# atmega.net
KiCad netlist of a schematic drawn in Altium Designer
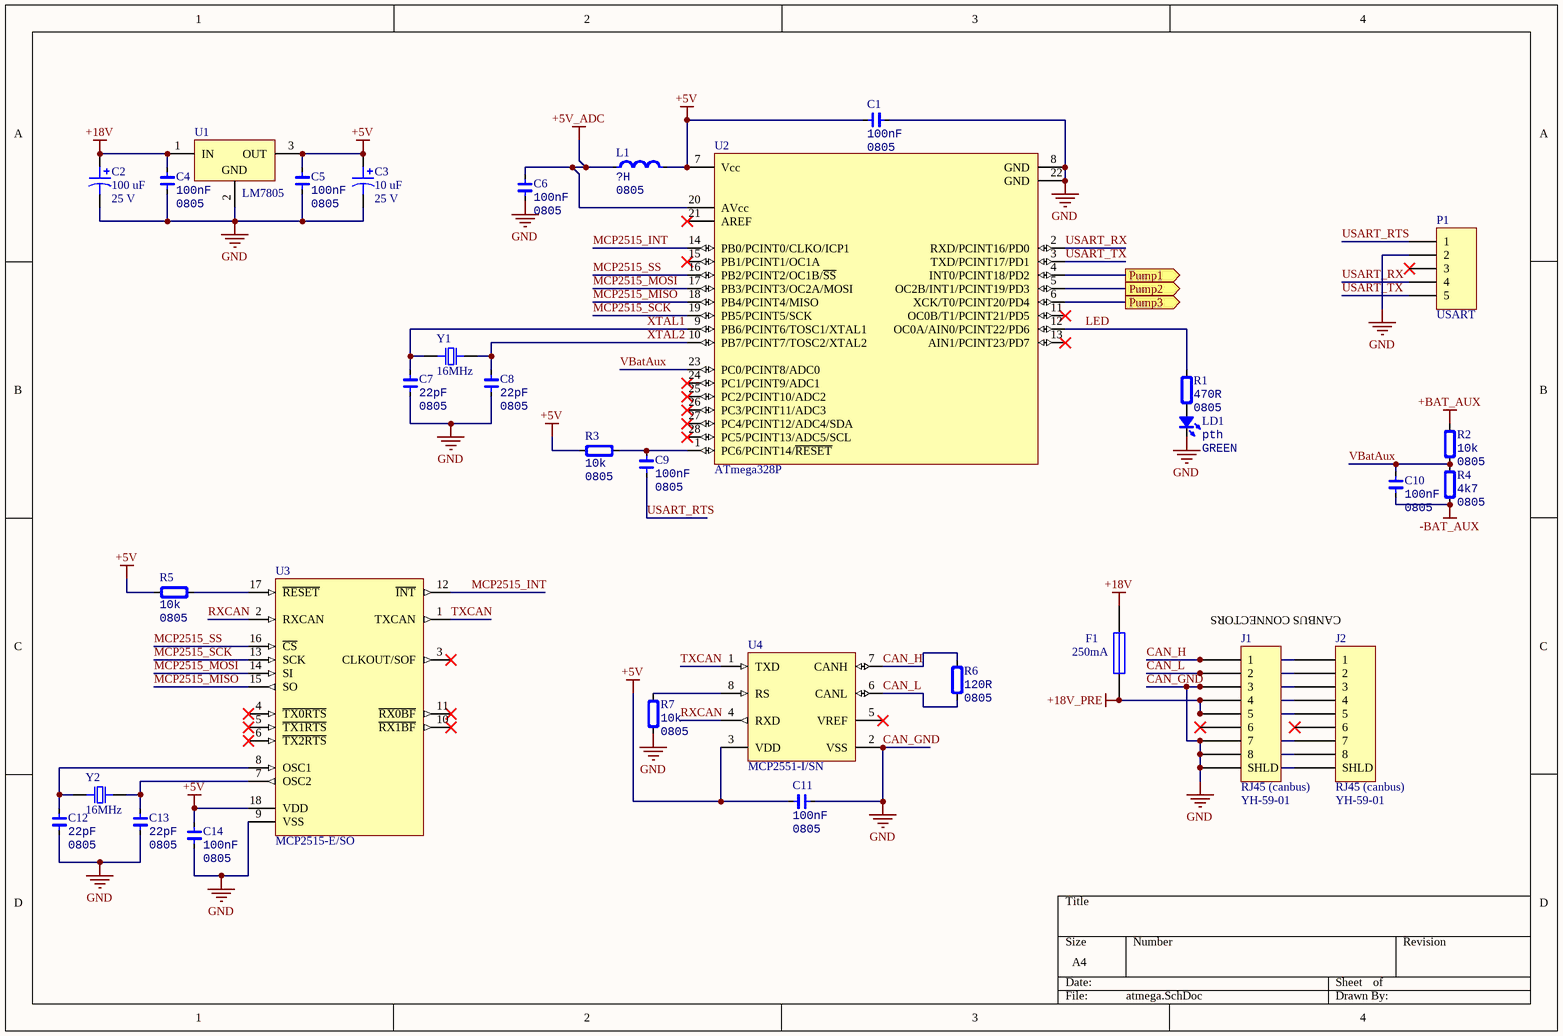
[diagram p0: atmega.SchDoc]

(export (version "E")
  (design (tool "Eeschema 10.0.6"))
  (components
    (comp (ref "C1")
      (value "100nF")
      (footprint "0805C")
      (description "Capacitor")
      (fields (field (name "TYPE") "0805"))
      (libsource (lib "") (part "Cap_0805_1"))
    )
    (comp (ref "C2")
      (value "100 uF")
      (footprint "CP3.5mm-8.0mm")
      (description "Solid Aluminum Capacitor with Organic Semiconductor Electrolyte: 100uF, 10V, Bulk Pack")
      (fields (field (name "VOLTAGE") "25 V"))
      (libsource (lib "R2R - Nova") (part "CapacitorPol"))
    )
    (comp (ref "C3")
      (value "10 uF")
      (footprint "CP3.5mm-8.0mm")
      (description "Solid Aluminum Capacitor with Organic Semiconductor Electrolyte: 100uF, 10V, Bulk Pack")
      (fields (field (name "VOLTAGE") "25 V"))
      (libsource (lib "R2R - Nova") (part "CapacitorPol"))
    )
    (comp (ref "C4")
      (value "100nF")
      (footprint "0805C")
      (description "Capacitor")
      (fields (field (name "TYPE") "0805"))
      (libsource (lib "") (part "Cap_0805_2"))
    )
    (comp (ref "C5")
      (value "100nF")
      (footprint "0805C")
      (description "Capacitor")
      (fields (field (name "TYPE") "0805"))
      (libsource (lib "") (part "Cap_0805_2"))
    )
    (comp (ref "C6")
      (value "100nF")
      (footprint "0805C")
      (description "Capacitor")
      (fields (field (name "TYPE") "0805"))
      (libsource (lib "") (part "Cap_0805_2"))
    )
    (comp (ref "C7")
      (value "22pF")
      (footprint "0805C")
      (description "Capacitor")
      (fields (field (name "TYPE") "0805"))
      (libsource (lib "") (part "Cap_0805_2"))
    )
    (comp (ref "C8")
      (value "22pF")
      (footprint "0805C")
      (description "Capacitor")
      (fields (field (name "TYPE") "0805"))
      (libsource (lib "") (part "Cap_0805_2"))
    )
    (comp (ref "C9")
      (value "100nF")
      (footprint "0805C")
      (description "Capacitor")
      (fields (field (name "TYPE") "0805"))
      (libsource (lib "SCH_Passive") (part "Cap_0805"))
    )
    (comp (ref "C10")
      (value "100nF")
      (footprint "0805C")
      (description "Capacitor")
      (fields (field (name "TYPE") "0805"))
      (libsource (lib "") (part "Cap_0805_1"))
    )
    (comp (ref "C11")
      (value "100nF")
      (footprint "0805C")
      (description "Capacitor")
      (fields (field (name "TYPE") "0805"))
      (libsource (lib "") (part "Cap_0805_1"))
    )
    (comp (ref "C12")
      (value "22pF")
      (footprint "0805C")
      (description "Capacitor")
      (fields (field (name "TYPE") "0805"))
      (libsource (lib "") (part "Cap_0805_2"))
    )
    (comp (ref "C13")
      (value "22pF")
      (footprint "0805C")
      (description "Capacitor")
      (fields (field (name "TYPE") "0805"))
      (libsource (lib "") (part "Cap_0805_2"))
    )
    (comp (ref "C14")
      (value "100nF")
      (footprint "0805C")
      (description "Capacitor")
      (fields (field (name "TYPE") "0805"))
      (libsource (lib "SCH_Passive") (part "Cap_0805"))
    )
    (comp (ref "F1")
      (value "250mA")
      (footprint "Porta Fusivel")
      (description "Fuse")
      (libsource (lib "Miscellaneous Devices") (part "Fuse 1"))
    )
    (comp (ref "J1")
      (value "RJ45 (canbus)")
      (footprint "ASSMANN A-2004-2-4-LP/FS")
      (description "YH-59-01")
      (fields (field (name "ALTIUM_VALUE") "YH-59-01"))
      (libsource (lib "Connectors") (part "Modular Jack with Shield"))
    )
    (comp (ref "J2")
      (value "RJ45 (canbus)")
      (footprint "ASSMANN A-2004-2-4-LP/FS")
      (description "YH-59-01")
      (fields (field (name "ALTIUM_VALUE") "YH-59-01"))
      (libsource (lib "Connectors") (part "Modular Jack with Shield"))
    )
    (comp (ref "L1")
      (value "?H")
      (footprint "0805L")
      (description "Inductor")
      (fields (field (name "TYPE") "0805"))
      (libsource (lib "SCH_Passive") (part "Ind_0805"))
    )
    (comp (ref "LD1")
      (value "GREEN")
      (footprint "LED3MM")
      (description "LED")
      (fields (field (name "TYPE") "pth"))
      (libsource (lib "SCH_Active") (part "LED_0805"))
    )
    (comp (ref "P1")
      (value "USART")
      (footprint "Zenite_Footprints:HDR1X5")
      (description "Header, 5-Pin")
      (libsource (lib "R2R - Nova") (part "Header 5"))
    )
    (comp (ref "R1")
      (value "470R")
      (footprint "0805R")
      (description "Resistor")
      (fields (field (name "TYPE") "0805"))
      (libsource (lib "SCH_Passive") (part "Res_0805"))
    )
    (comp (ref "R2")
      (value "10k")
      (footprint "0805R")
      (description "Resistor")
      (fields (field (name "TYPE") "0805"))
      (libsource (lib "SCH_Passive") (part "Res_0805"))
    )
    (comp (ref "R3")
      (value "10k")
      (footprint "0805R")
      (description "Resistor")
      (fields (field (name "TYPE") "0805"))
      (libsource (lib "SCH_Passive") (part "Res_0805"))
    )
    (comp (ref "R4")
      (value "4k7")
      (footprint "0805R")
      (description "Resistor")
      (fields (field (name "TYPE") "0805"))
      (libsource (lib "SCH_Passive") (part "Res_0805"))
    )
    (comp (ref "R5")
      (value "10k")
      (footprint "0805R")
      (description "Resistor")
      (fields (field (name "TYPE") "0805"))
      (libsource (lib "SCH_Passive") (part "Res_0805"))
    )
    (comp (ref "R6")
      (value "120R")
      (footprint "0805R")
      (description "Resistor")
      (fields (field (name "TYPE") "0805"))
      (libsource (lib "SCH_Passive") (part "Res_0805"))
    )
    (comp (ref "R7")
      (value "10k")
      (footprint "0805R")
      (description "Resistor")
      (fields (field (name "TYPE") "0805"))
      (libsource (lib "SCH_Passive") (part "Res_0805"))
    )
    (comp (ref "U1")
      (value "LM7805")
      (footprint "TO220_deitado")
      (description "Positive-Voltage Regulator")
      (libsource (lib "TI Power Mgt Voltage Regulator") (part "µA7805CKC"))
    )
    (comp (ref "U2")
      (value "ATmega328P")
      (footprint "DIP28-300(100)")
      (libsource (lib "R2R - Nova") (part "ATmega328P"))
    )
    (comp (ref "U3")
      (value "MCP2515-E/SO")
      (footprint "WSO18_L")
      (description "Stand-Alone CAN Controller With SPI Interface, 18-Pin SOIC, Extended Temperature")
      (libsource (lib "Altium Content Vault") (part "COM-CAN-MCP2515-18"))
    )
    (comp (ref "U4")
      (value "MCP2551-I/SN")
      (footprint "SOIC08-150(50)")
      (libsource (lib "Altium Content Vault") (part "MCHP-MCP2551-SN8"))
    )
    (comp (ref "Y1")
      (value "16MHz")
      (footprint "HC49-US-THT")
      (description "Crystal")
      (libsource (lib "R2R - Nova") (part "Crystal"))
    )
    (comp (ref "Y2")
      (value "16MHz")
      (footprint "HC49-US-THT")
      (description "Crystal")
      (libsource (lib "R2R - Nova") (part "Crystal"))
    )
  )
  (nets
    (net (code "1") (name "+5V") (class "Default")
      (node (ref "C1") (pin "1") (pinfunction "1_1") (pintype "passive"))
      (node (ref "C11") (pin "1") (pinfunction "1_1") (pintype "passive"))
      (node (ref "C14") (pin "1") (pinfunction "1_1") (pintype "passive"))
      (node (ref "C3") (pin "1") (pinfunction "1_1") (pintype "passive"))
      (node (ref "C5") (pin "2") (pinfunction "2_2") (pintype "passive"))
      (node (ref "L1") (pin "2") (pinfunction "2_2") (pintype "passive"))
      (node (ref "R3") (pin "1") (pinfunction "1_1") (pintype "passive"))
      (node (ref "R5") (pin "1") (pinfunction "1_1") (pintype "passive"))
      (node (ref "U1") (pin "3") (pinfunction "OUT_3") (pintype "power_in"))
      (node (ref "U2") (pin "7") (pinfunction "Vcc_7") (pintype "passive"))
      (node (ref "U3") (pin "18") (pinfunction "VDD_18") (pintype "power_in"))
      (node (ref "U4") (pin "3") (pinfunction "VDD_3") (pintype "power_in"))
    )
    (net (code "2") (name "+5V_ADC") (class "Default")
      (node (ref "C6") (pin "2") (pinfunction "2_2") (pintype "passive"))
      (node (ref "L1") (pin "1") (pinfunction "1_1") (pintype "passive"))
      (node (ref "U2") (pin "20") (pinfunction "AVcc_20") (pintype "passive"))
    )
    (net (code "3") (name "+18V") (class "Default")
      (node (ref "C2") (pin "1") (pinfunction "1_1") (pintype "passive"))
      (node (ref "C4") (pin "2") (pinfunction "2_2") (pintype "passive"))
      (node (ref "F1") (pin "1") (pinfunction "1_1") (pintype "passive"))
      (node (ref "U1") (pin "1") (pinfunction "IN_1") (pintype "power_in"))
    )
    (net (code "4") (name "+18V_PRE") (class "Default")
      (node (ref "F1") (pin "2") (pinfunction "2_2") (pintype "passive"))
      (node (ref "J1") (pin "4") (pinfunction "4_4") (pintype "passive"))
      (node (ref "J1") (pin "5") (pinfunction "5_5") (pintype "passive"))
      (node (ref "J2") (pin "4") (pinfunction "4_4") (pintype "passive"))
      (node (ref "J2") (pin "5") (pinfunction "5_5") (pintype "passive"))
    )
    (net (code "5") (name "+BAT_AUX") (class "Default")
      (node (ref "R2") (pin "2") (pinfunction "2_2") (pintype "passive"))
    )
    (net (code "6") (name "-BAT_AUX") (class "Default")
      (node (ref "C10") (pin "1") (pinfunction "1_1") (pintype "passive"))
      (node (ref "R4") (pin "1") (pinfunction "1_1") (pintype "passive"))
    )
    (net (code "7") (name "/CAN_H") (class "Default")
      (node (ref "J1") (pin "1") (pinfunction "1_1") (pintype "passive"))
      (node (ref "J2") (pin "1") (pinfunction "1_1") (pintype "passive"))
      (node (ref "R6") (pin "2") (pinfunction "2_2") (pintype "passive"))
      (node (ref "U4") (pin "7") (pinfunction "CANH_7") (pintype "bidirectional"))
    )
    (net (code "8") (name "/CAN_L") (class "Default")
      (node (ref "J1") (pin "2") (pinfunction "2_2") (pintype "passive"))
      (node (ref "J2") (pin "2") (pinfunction "2_2") (pintype "passive"))
      (node (ref "R6") (pin "1") (pinfunction "1_1") (pintype "passive"))
      (node (ref "U4") (pin "6") (pinfunction "CANL_6") (pintype "bidirectional"))
    )
    (net (code "9") (name "/LED") (class "Default")
      (node (ref "R1") (pin "2") (pinfunction "2_2") (pintype "passive"))
      (node (ref "U2") (pin "12") (pinfunction "OC0A/AIN0/PCINT22/PD6_12") (pintype "bidirectional"))
    )
    (net (code "10") (name "/MCP2515_INT") (class "Default")
      (node (ref "U2") (pin "14") (pinfunction "PB0/PCINT0/CLKO/ICP1_14") (pintype "bidirectional"))
      (node (ref "U3") (pin "12") (pinfunction "~{INT}_12") (pintype "output"))
    )
    (net (code "11") (name "/MCP2515_MISO") (class "Default")
      (node (ref "U2") (pin "18") (pinfunction "PB4/PCINT4/MISO_18") (pintype "bidirectional"))
      (node (ref "U3") (pin "15") (pinfunction "SO_15") (pintype "output"))
    )
    (net (code "12") (name "/MCP2515_MOSI") (class "Default")
      (node (ref "U2") (pin "17") (pinfunction "PB3/PCINT3/OC2A/MOSI_17") (pintype "bidirectional"))
      (node (ref "U3") (pin "14") (pinfunction "SI_14") (pintype "input"))
    )
    (net (code "13") (name "/MCP2515_SCK") (class "Default")
      (node (ref "U2") (pin "19") (pinfunction "PB5/PCINT5/SCK_19") (pintype "bidirectional"))
      (node (ref "U3") (pin "13") (pinfunction "SCK_13") (pintype "input"))
    )
    (net (code "14") (name "/MCP2515_SS") (class "Default")
      (node (ref "U2") (pin "16") (pinfunction "PB2/PCINT2/OC1B/~{SS}_16") (pintype "bidirectional"))
      (node (ref "U3") (pin "16") (pinfunction "~{CS}_16") (pintype "input"))
    )
    (net (code "15") (name "/Pump1") (class "Default")
      (node (ref "U2") (pin "4") (pinfunction "INT0/PCINT18/PD2_4") (pintype "bidirectional"))
    )
    (net (code "16") (name "/Pump2") (class "Default")
      (node (ref "U2") (pin "5") (pinfunction "OC2B/INT1/PCINT19/PD3_5") (pintype "bidirectional"))
    )
    (net (code "17") (name "/Pump3") (class "Default")
      (node (ref "U2") (pin "6") (pinfunction "XCK/T0/PCINT20/PD4_6") (pintype "bidirectional"))
    )
    (net (code "18") (name "/RXCAN") (class "Default")
      (node (ref "U3") (pin "2") (pinfunction "RXCAN_2") (pintype "input"))
      (node (ref "U4") (pin "4") (pinfunction "RXD_4") (pintype "output"))
    )
    (net (code "19") (name "/TXCAN") (class "Default")
      (node (ref "U3") (pin "1") (pinfunction "TXCAN_1") (pintype "output"))
      (node (ref "U4") (pin "1") (pinfunction "TXD_1") (pintype "input"))
    )
    (net (code "20") (name "/USART_RTS") (class "Default")
      (node (ref "C9") (pin "2") (pinfunction "2_2") (pintype "passive"))
      (node (ref "P1") (pin "1") (pinfunction "1_1") (pintype "passive"))
    )
    (net (code "21") (name "/USART_RX") (class "Default")
      (node (ref "P1") (pin "4") (pinfunction "4_4") (pintype "passive"))
      (node (ref "U2") (pin "2") (pinfunction "RXD/PCINT16/PD0_2") (pintype "bidirectional"))
    )
    (net (code "22") (name "/USART_TX") (class "Default")
      (node (ref "P1") (pin "5") (pinfunction "5_5") (pintype "passive"))
      (node (ref "U2") (pin "3") (pinfunction "TXD/PCINT17/PD1_3") (pintype "bidirectional"))
    )
    (net (code "23") (name "/VBatAux") (class "Default")
      (node (ref "C10") (pin "2") (pinfunction "2_2") (pintype "passive"))
      (node (ref "R2") (pin "1") (pinfunction "1_1") (pintype "passive"))
      (node (ref "R4") (pin "2") (pinfunction "2_2") (pintype "passive"))
      (node (ref "U2") (pin "23") (pinfunction "PC0/PCINT8/ADC0_23") (pintype "bidirectional"))
    )
    (net (code "24") (name "/XTAL1") (class "Default")
      (node (ref "C7") (pin "2") (pinfunction "2_2") (pintype "passive"))
      (node (ref "U2") (pin "9") (pinfunction "PB6/PCINT6/TOSC1/XTAL1_9") (pintype "bidirectional"))
      (node (ref "Y1") (pin "1") (pinfunction "1_1") (pintype "passive"))
    )
    (net (code "25") (name "/XTAL2") (class "Default")
      (node (ref "C8") (pin "2") (pinfunction "2_2") (pintype "passive"))
      (node (ref "U2") (pin "10") (pinfunction "PB7/PCINT7/TOSC2/XTAL2_10") (pintype "bidirectional"))
      (node (ref "Y1") (pin "2") (pinfunction "2_2") (pintype "passive"))
    )
    (net (code "26") (name "GND") (class "Default")
      (node (ref "C1") (pin "2") (pinfunction "2_2") (pintype "passive"))
      (node (ref "C11") (pin "2") (pinfunction "2_2") (pintype "passive"))
      (node (ref "C12") (pin "1") (pinfunction "1_1") (pintype "passive"))
      (node (ref "C13") (pin "1") (pinfunction "1_1") (pintype "passive"))
      (node (ref "C14") (pin "2") (pinfunction "2_2") (pintype "passive"))
      (node (ref "C2") (pin "2") (pinfunction "2_2") (pintype "passive"))
      (node (ref "C3") (pin "2") (pinfunction "2_2") (pintype "passive"))
      (node (ref "C4") (pin "1") (pinfunction "1_1") (pintype "passive"))
      (node (ref "C5") (pin "1") (pinfunction "1_1") (pintype "passive"))
      (node (ref "C6") (pin "1") (pinfunction "1_1") (pintype "passive"))
      (node (ref "C7") (pin "1") (pinfunction "1_1") (pintype "passive"))
      (node (ref "C8") (pin "1") (pinfunction "1_1") (pintype "passive"))
      (node (ref "J1") (pin "3") (pinfunction "3_3") (pintype "passive"))
      (node (ref "J1") (pin "7") (pinfunction "7_7") (pintype "passive"))
      (node (ref "J1") (pin "8") (pinfunction "8_8") (pintype "passive"))
      (node (ref "J1") (pin "S") (pinfunction "SHLD_S") (pintype "passive"))
      (node (ref "J2") (pin "3") (pinfunction "3_3") (pintype "passive"))
      (node (ref "J2") (pin "7") (pinfunction "7_7") (pintype "passive"))
      (node (ref "J2") (pin "8") (pinfunction "8_8") (pintype "passive"))
      (node (ref "J2") (pin "S") (pinfunction "SHLD_S") (pintype "passive"))
      (node (ref "LD1") (pin "2") (pinfunction "K_2") (pintype "passive"))
      (node (ref "P1") (pin "2") (pinfunction "2_2") (pintype "passive"))
      (node (ref "R7") (pin "2") (pinfunction "2_2") (pintype "passive"))
      (node (ref "U1") (pin "2") (pinfunction "GND_2") (pintype "power_in"))
      (node (ref "U2") (pin "22") (pinfunction "GND_22") (pintype "passive"))
      (node (ref "U2") (pin "8") (pinfunction "GND_8") (pintype "passive"))
      (node (ref "U3") (pin "9") (pinfunction "VSS_9") (pintype "power_in"))
      (node (ref "U4") (pin "2") (pinfunction "VSS_2") (pintype "power_in"))
    )
    (net (code "27") (name "Net-(LD1-A)") (class "Default")
      (node (ref "LD1") (pin "1") (pinfunction "A_1") (pintype "passive"))
      (node (ref "R1") (pin "1") (pinfunction "1_1") (pintype "passive"))
    )
    (net (code "28") (name "Net-(U2-PC6{slash}PCINT14{slash}~{RESET})") (class "Default")
      (node (ref "C9") (pin "1") (pinfunction "1_1") (pintype "passive"))
      (node (ref "R3") (pin "2") (pinfunction "2_2") (pintype "passive"))
      (node (ref "U2") (pin "1") (pinfunction "PC6/PCINT14/~{RESET}_1") (pintype "bidirectional"))
    )
    (net (code "29") (name "Net-(U3-OSC1)") (class "Default")
      (node (ref "C12") (pin "2") (pinfunction "2_2") (pintype "passive"))
      (node (ref "U3") (pin "8") (pinfunction "OSC1_8") (pintype "input"))
      (node (ref "Y2") (pin "1") (pinfunction "1_1") (pintype "passive"))
    )
    (net (code "30") (name "Net-(U3-OSC2)") (class "Default")
      (node (ref "C13") (pin "2") (pinfunction "2_2") (pintype "passive"))
      (node (ref "U3") (pin "7") (pinfunction "OSC2_7") (pintype "output"))
      (node (ref "Y2") (pin "2") (pinfunction "2_2") (pintype "passive"))
    )
    (net (code "31") (name "Net-(U3-~{RESET})") (class "Default")
      (node (ref "R5") (pin "2") (pinfunction "2_2") (pintype "passive"))
      (node (ref "U3") (pin "17") (pinfunction "~{RESET}_17") (pintype "input"))
    )
    (net (code "32") (name "Net-(U4-RS)") (class "Default")
      (node (ref "R7") (pin "1") (pinfunction "1_1") (pintype "passive"))
      (node (ref "U4") (pin "8") (pinfunction "RS_8") (pintype "input"))
    )
    (net (code "33") (name "unconnected-(J1-Pad6)") (class "Default")
      (node (ref "J1") (pin "6") (pinfunction "6_6") (pintype "passive+no_connect"))
    )
    (net (code "34") (name "unconnected-(J2-Pad6)") (class "Default")
      (node (ref "J2") (pin "6") (pinfunction "6_6") (pintype "passive+no_connect"))
    )
    (net (code "35") (name "unconnected-(P1-Pad3)") (class "Default")
      (node (ref "P1") (pin "3") (pinfunction "3_3") (pintype "passive+no_connect"))
    )
    (net (code "36") (name "unconnected-(U2-AIN1{slash}PCINT23{slash}PD7-Pad13)") (class "Default")
      (node (ref "U2") (pin "13") (pinfunction "AIN1/PCINT23/PD7_13") (pintype "bidirectional+no_connect"))
    )
    (net (code "37") (name "unconnected-(U2-AREF-Pad21)") (class "Default")
      (node (ref "U2") (pin "21") (pinfunction "AREF_21") (pintype "passive+no_connect"))
    )
    (net (code "38") (name "unconnected-(U2-OC0B{slash}T1{slash}PCINT21{slash}PD5-Pad11)") (class "Default")
      (node (ref "U2") (pin "11") (pinfunction "OC0B/T1/PCINT21/PD5_11") (pintype "bidirectional+no_connect"))
    )
    (net (code "39") (name "unconnected-(U2-PB1{slash}PCINT1{slash}OC1A-Pad15)") (class "Default")
      (node (ref "U2") (pin "15") (pinfunction "PB1/PCINT1/OC1A_15") (pintype "bidirectional+no_connect"))
    )
    (net (code "40") (name "unconnected-(U2-PC1{slash}PCINT9{slash}ADC1-Pad24)") (class "Default")
      (node (ref "U2") (pin "24") (pinfunction "PC1/PCINT9/ADC1_24") (pintype "bidirectional+no_connect"))
    )
    (net (code "41") (name "unconnected-(U2-PC2{slash}PCINT10{slash}ADC2-Pad25)") (class "Default")
      (node (ref "U2") (pin "25") (pinfunction "PC2/PCINT10/ADC2_25") (pintype "bidirectional+no_connect"))
    )
    (net (code "42") (name "unconnected-(U2-PC3{slash}PCINT11{slash}ADC3-Pad26)") (class "Default")
      (node (ref "U2") (pin "26") (pinfunction "PC3/PCINT11/ADC3_26") (pintype "bidirectional+no_connect"))
    )
    (net (code "43") (name "unconnected-(U2-PC4{slash}PCINT12{slash}ADC4{slash}SDA-Pad27)") (class "Default")
      (node (ref "U2") (pin "27") (pinfunction "PC4/PCINT12/ADC4/SDA_27") (pintype "bidirectional+no_connect"))
    )
    (net (code "44") (name "unconnected-(U2-PC5{slash}PCINT13{slash}ADC5{slash}SCL-Pad28)") (class "Default")
      (node (ref "U2") (pin "28") (pinfunction "PC5/PCINT13/ADC5/SCL_28") (pintype "bidirectional+no_connect"))
    )
    (net (code "45") (name "unconnected-(U3-CLKOUT{slash}SOF-Pad3)") (class "Default")
      (node (ref "U3") (pin "3") (pinfunction "CLKOUT/SOF_3") (pintype "output+no_connect"))
    )
    (net (code "46") (name "unconnected-(U3-~{RX0BF}-Pad11)") (class "Default")
      (node (ref "U3") (pin "11") (pinfunction "~{RX0BF}_11") (pintype "output+no_connect"))
    )
    (net (code "47") (name "unconnected-(U3-~{RX1BF}-Pad10)") (class "Default")
      (node (ref "U3") (pin "10") (pinfunction "~{RX1BF}_10") (pintype "output+no_connect"))
    )
    (net (code "48") (name "unconnected-(U3-~{TX0RTS}-Pad4)") (class "Default")
      (node (ref "U3") (pin "4") (pinfunction "~{TX0RTS}_4") (pintype "input+no_connect"))
    )
    (net (code "49") (name "unconnected-(U3-~{TX1RTS}-Pad5)") (class "Default")
      (node (ref "U3") (pin "5") (pinfunction "~{TX1RTS}_5") (pintype "input+no_connect"))
    )
    (net (code "50") (name "unconnected-(U3-~{TX2RTS}-Pad6)") (class "Default")
      (node (ref "U3") (pin "6") (pinfunction "~{TX2RTS}_6") (pintype "input+no_connect"))
    )
    (net (code "51") (name "unconnected-(U4-VREF-Pad5)") (class "Default")
      (node (ref "U4") (pin "5") (pinfunction "VREF_5") (pintype "power_in+no_connect"))
    )
  )
)
